# Dashboard_rev2.net
KiCad netlist of a schematic drawn in EAGLE
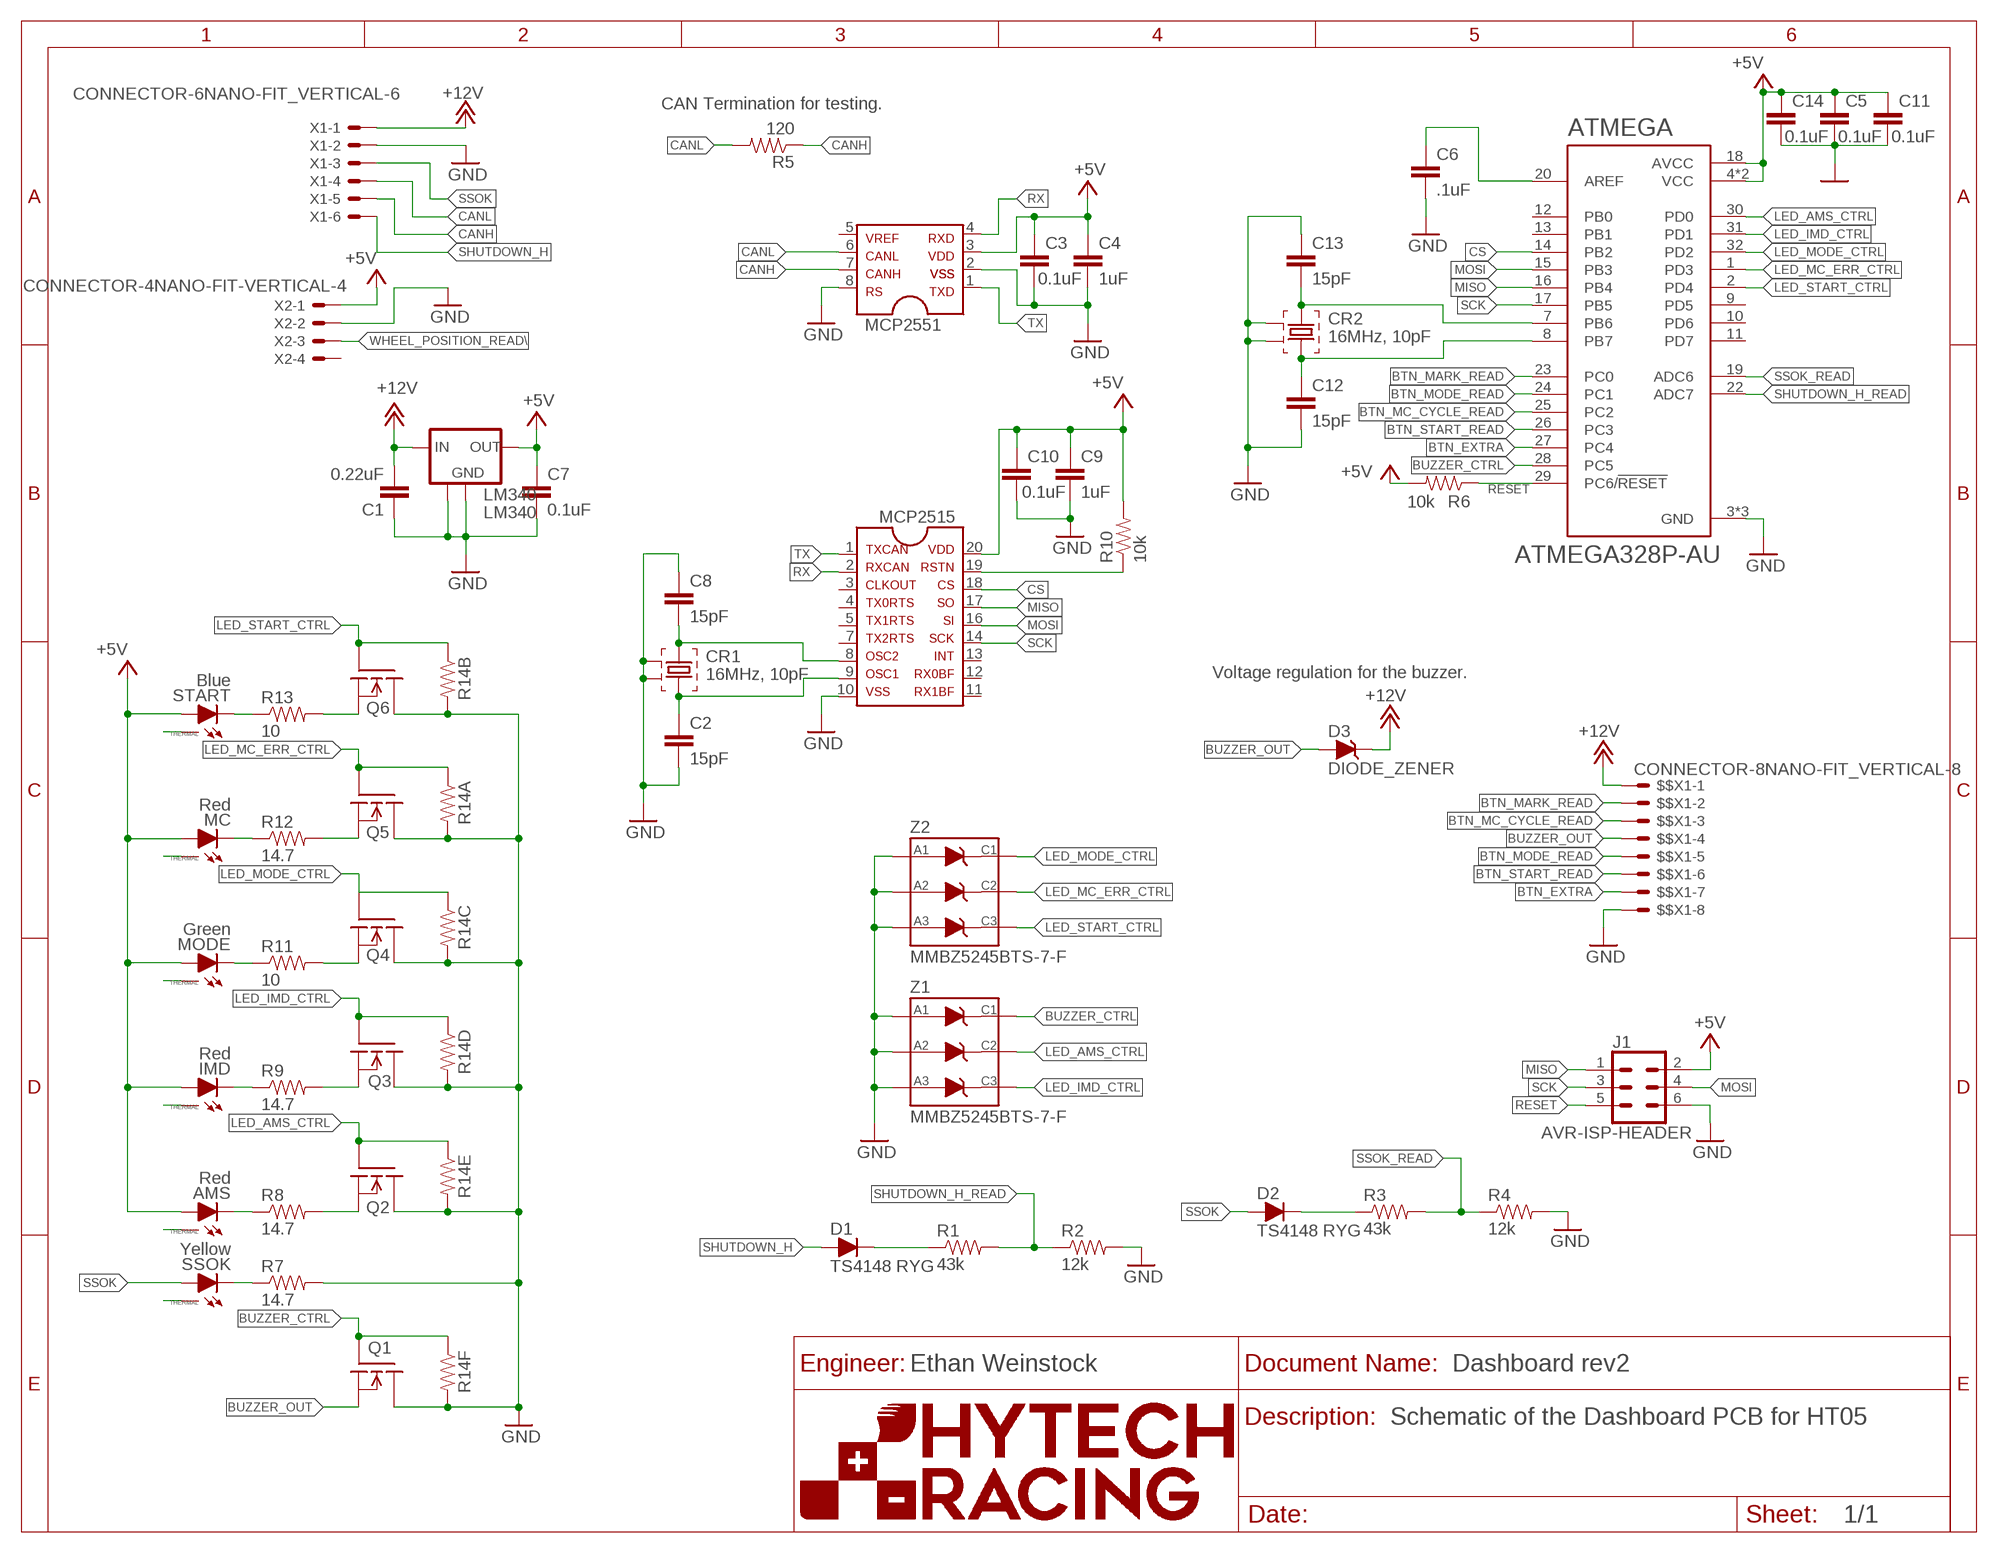
[diagram p0: schematic, sheet 1]

(export (version "E")
  (design (tool "Eeschema 10.0.6"))
  (components
    (comp (ref "$$X1")
      (value "CONNECTOR-8NANO-FIT_VERTICAL-8")
      (footprint "eagle-import:NANO-FIT_VERTICAL-8")
      (libsource (lib "eagle-import") (part "CONNECTOR-8NANO-FIT_VERTICAL-8"))
    )
    (comp (ref "AMS")
      (value "Red")
      (footprint "eagle-import:XP-E2")
      (libsource (lib "eagle-import") (part "XP-E2XP-E2"))
    )
    (comp (ref "ATMEGA")
      (value "ATMEGA328P-AU")
      (footprint "eagle-import:QFP80P900X900X120-32N")
      (fields (field (name "MF") "Microchip"))
      (libsource (lib "eagle-import") (part "ATMEGA328P-AU"))
    )
    (comp (ref "C1")
      (value "0.22uF")
      (footprint "eagle-import:0603-CAP")
      (libsource (lib "eagle-import") (part "CAP0603-CAP"))
    )
    (comp (ref "C2")
      (value "15pF")
      (footprint "eagle-import:0603-CAP")
      (libsource (lib "eagle-import") (part "CAP0603-CAP"))
    )
    (comp (ref "C3")
      (value "0.1uF")
      (footprint "eagle-import:0603-CAP")
      (libsource (lib "eagle-import") (part "CAP0603-CAP"))
    )
    (comp (ref "C4")
      (value "1uF")
      (footprint "eagle-import:0603-CAP")
      (libsource (lib "eagle-import") (part "CAP0603-CAP"))
    )
    (comp (ref "C5")
      (value "0.1uF")
      (footprint "eagle-import:0603-CAP")
      (libsource (lib "eagle-import") (part "CAP0603-CAP"))
    )
    (comp (ref "C6")
      (value ".1uF")
      (footprint "eagle-import:0603-CAP")
      (libsource (lib "eagle-import") (part "CAP0603-CAP"))
    )
    (comp (ref "C7")
      (value "0.1uF")
      (footprint "eagle-import:0603-CAP")
      (libsource (lib "eagle-import") (part "CAP0603-CAP"))
    )
    (comp (ref "C8")
      (value "15pF")
      (footprint "eagle-import:0603-CAP")
      (libsource (lib "eagle-import") (part "CAP0603-CAP"))
    )
    (comp (ref "C9")
      (value "1uF")
      (footprint "eagle-import:0603-CAP")
      (libsource (lib "eagle-import") (part "CAP0603-CAP"))
    )
    (comp (ref "C10")
      (value "0.1uF")
      (footprint "eagle-import:0603-CAP")
      (libsource (lib "eagle-import") (part "CAP0603-CAP"))
    )
    (comp (ref "C11")
      (value "0.1uF")
      (footprint "eagle-import:0603-CAP")
      (libsource (lib "eagle-import") (part "CAP0603-CAP"))
    )
    (comp (ref "C12")
      (value "15pF")
      (footprint "eagle-import:0603-CAP")
      (libsource (lib "eagle-import") (part "CAP0603-CAP"))
    )
    (comp (ref "C13")
      (value "15pF")
      (footprint "eagle-import:0603-CAP")
      (libsource (lib "eagle-import") (part "CAP0603-CAP"))
    )
    (comp (ref "C14")
      (value "0.1uF")
      (footprint "eagle-import:0603-CAP")
      (libsource (lib "eagle-import") (part "CAP0603-CAP"))
    )
    (comp (ref "CR1")
      (value "16MHz, 10pF")
      (footprint "eagle-import:ABM3B")
      (libsource (lib "eagle-import") (part "ABM3B"))
    )
    (comp (ref "CR2")
      (value "16MHz, 10pF")
      (footprint "eagle-import:ABM3B")
      (libsource (lib "eagle-import") (part "ABM3B"))
    )
    (comp (ref "D1")
      (value "TS4148 RYG")
      (footprint "eagle-import:0805_D")
      (libsource (lib "eagle-import") (part "DIODE0805"))
    )
    (comp (ref "D2")
      (value "TS4148 RYG")
      (footprint "eagle-import:0805_D")
      (libsource (lib "eagle-import") (part "DIODE0805"))
    )
    (comp (ref "D3")
      (value "DIODE_ZENER")
      (footprint "eagle-import:SOT23")
      (libsource (lib "eagle-import") (part "DIODE_ZENER"))
    )
    (comp (ref "IMD")
      (value "Red")
      (footprint "eagle-import:XP-E2")
      (libsource (lib "eagle-import") (part "XP-E2XP-E2"))
    )
    (comp (ref "J1")
      (value "AVR-ISP-HEADER")
      (footprint "eagle-import:2X03")
      (libsource (lib "eagle-import") (part "AVR-ISP-HEADER"))
    )
    (comp (ref "LM340")
      (value "LM340")
      (footprint "eagle-import:SOT223")
      (libsource (lib "eagle-import") (part "LM340"))
    )
    (comp (ref "MC")
      (value "Red")
      (footprint "eagle-import:XP-E2")
      (libsource (lib "eagle-import") (part "XP-E2XP-E2"))
    )
    (comp (ref "MCP2515")
      (value "MCP2515TSSOP")
      (footprint "eagle-import:TSSOP-20")
      (libsource (lib "eagle-import") (part "MCP2515TSSOP"))
    )
    (comp (ref "MCP2551")
      (value "MCP2551")
      (footprint "eagle-import:SOIC-08")
      (libsource (lib "eagle-import") (part "MCP2551"))
    )
    (comp (ref "MODE")
      (value "Green")
      (footprint "eagle-import:XP-E2")
      (libsource (lib "eagle-import") (part "XP-E2XP-E2"))
    )
    (comp (ref "Q1")
      (value "DMG3406LSOT")
      (footprint "eagle-import:SOT23")
      (libsource (lib "eagle-import") (part "DMG3406LSOT"))
    )
    (comp (ref "Q2")
      (value "DMG3406LSOT")
      (footprint "eagle-import:SOT23")
      (libsource (lib "eagle-import") (part "DMG3406LSOT"))
    )
    (comp (ref "Q3")
      (value "DMG3406LSOT")
      (footprint "eagle-import:SOT23")
      (libsource (lib "eagle-import") (part "DMG3406LSOT"))
    )
    (comp (ref "Q4")
      (value "DMG3406LSOT")
      (footprint "eagle-import:SOT23")
      (libsource (lib "eagle-import") (part "DMG3406LSOT"))
    )
    (comp (ref "Q5")
      (value "DMG3406LSOT")
      (footprint "eagle-import:SOT23")
      (libsource (lib "eagle-import") (part "DMG3406LSOT"))
    )
    (comp (ref "Q6")
      (value "DMG3406LSOT")
      (footprint "eagle-import:SOT23")
      (libsource (lib "eagle-import") (part "DMG3406LSOT"))
    )
    (comp (ref "R1")
      (value "43k")
      (footprint "eagle-import:0603-RES")
      (libsource (lib "eagle-import") (part "RESISTOR0603"))
    )
    (comp (ref "R2")
      (value "12k")
      (footprint "eagle-import:0603-RES")
      (libsource (lib "eagle-import") (part "RESISTOR0603"))
    )
    (comp (ref "R3")
      (value "43k")
      (footprint "eagle-import:0603-RES")
      (libsource (lib "eagle-import") (part "RESISTOR0603"))
    )
    (comp (ref "R4")
      (value "12k")
      (footprint "eagle-import:0603-RES")
      (libsource (lib "eagle-import") (part "RESISTOR0603"))
    )
    (comp (ref "R5")
      (value "120")
      (footprint "eagle-import:0603-RES")
      (libsource (lib "eagle-import") (part "RESISTOR0603-RES"))
    )
    (comp (ref "R6")
      (value "10k")
      (footprint "eagle-import:0603-RES")
      (libsource (lib "eagle-import") (part "RESISTOR0603"))
    )
    (comp (ref "R7")
      (value "14.7")
      (footprint "eagle-import:0603-RES")
      (libsource (lib "eagle-import") (part "RESISTOR0603"))
    )
    (comp (ref "R8")
      (value "14.7")
      (footprint "eagle-import:0603-RES")
      (libsource (lib "eagle-import") (part "RESISTOR0603"))
    )
    (comp (ref "R9")
      (value "14.7")
      (footprint "eagle-import:0603-RES")
      (libsource (lib "eagle-import") (part "RESISTOR0603"))
    )
    (comp (ref "R10")
      (value "10k")
      (footprint "eagle-import:0603-RES")
      (libsource (lib "eagle-import") (part "RESISTOR0603"))
    )
    (comp (ref "R11")
      (value "10")
      (footprint "eagle-import:0603-RES")
      (libsource (lib "eagle-import") (part "RESISTOR0603"))
    )
    (comp (ref "R12")
      (value "14.7")
      (footprint "eagle-import:0603-RES")
      (libsource (lib "eagle-import") (part "RESISTOR0603"))
    )
    (comp (ref "R13")
      (value "10")
      (footprint "eagle-import:0603-RES")
      (libsource (lib "eagle-import") (part "RESISTOR0603"))
    )
    (comp (ref "R14")
      (value "10k")
      (footprint "eagle-import:YAG_YC248-M")
      (fields (field (name "MANUFACTURER_PART_NUMBER") "YC248-JR-0710KL"))
      (libsource (lib "eagle-import") (part "YC248-JR-0710KL"))
    )
    (comp (ref "SSOK")
      (value "Yellow")
      (footprint "eagle-import:XP-E2")
      (libsource (lib "eagle-import") (part "XP-E2XP-E2"))
    )
    (comp (ref "START")
      (value "Blue")
      (footprint "eagle-import:XP-E2")
      (libsource (lib "eagle-import") (part "XP-E2XP-E2"))
    )
    (comp (ref "X1")
      (value "CONNECTOR-6NANO-FIT_VERTICAL-6")
      (footprint "eagle-import:NANO-FIT_VERTICAL-6")
      (libsource (lib "eagle-import") (part "CONNECTOR-6NANO-FIT_VERTICAL-6"))
    )
    (comp (ref "X2")
      (value "CONNECTOR-4NANO-FIT-VERTICAL-4")
      (footprint "eagle-import:NANO-FIT_VERTICAL-4")
      (libsource (lib "eagle-import") (part "CONNECTOR-4NANO-FIT-VERTICAL-4"))
    )
    (comp (ref "Z1")
      (value "MMBZ5245BTS-7-F")
      (footprint "eagle-import:SOT363")
      (fields (field (name "VOLTAGE") "15V"))
      (libsource (lib "eagle-import") (part "MMBZ5245BTS-7-F"))
    )
    (comp (ref "Z2")
      (value "MMBZ5245BTS-7-F")
      (footprint "eagle-import:SOT363")
      (fields (field (name "VOLTAGE") "15V"))
      (libsource (lib "eagle-import") (part "MMBZ5245BTS-7-F"))
    )
  )
  (nets
    (net (code "1") (name "+5V") (class "Default")
      (node (ref "AMS") (pin "A") (pinfunction "A_A") (pintype "passive"))
      (node (ref "ATMEGA") (pin "18") (pinfunction "AVCC_18") (pintype "power_in"))
      (node (ref "ATMEGA") (pin "4") (pinfunction "VCC_4") (pintype "power_in"))
      (node (ref "ATMEGA") (pin "6") (pinfunction "VCC_6") (pintype "power_in"))
      (node (ref "C10") (pin "1") (pinfunction "1_1") (pintype "passive"))
      (node (ref "C11") (pin "1") (pinfunction "1_1") (pintype "passive"))
      (node (ref "C14") (pin "1") (pinfunction "1_1") (pintype "passive"))
      (node (ref "C3") (pin "1") (pinfunction "1_1") (pintype "passive"))
      (node (ref "C4") (pin "1") (pinfunction "1_1") (pintype "passive"))
      (node (ref "C5") (pin "1") (pinfunction "1_1") (pintype "passive"))
      (node (ref "C7") (pin "1") (pinfunction "1_1") (pintype "passive"))
      (node (ref "C9") (pin "1") (pinfunction "1_1") (pintype "passive"))
      (node (ref "IMD") (pin "A") (pinfunction "A_A") (pintype "passive"))
      (node (ref "J1") (pin "2") (pinfunction "2_2") (pintype "passive"))
      (node (ref "LM340") (pin "3") (pinfunction "OUT_3") (pintype "output"))
      (node (ref "MC") (pin "A") (pinfunction "A_A") (pintype "passive"))
      (node (ref "MCP2515") (pin "20") (pinfunction "VDD_20") (pintype "passive"))
      (node (ref "MCP2551") (pin "3") (pinfunction "3_3") (pintype "passive"))
      (node (ref "MODE") (pin "A") (pinfunction "A_A") (pintype "passive"))
      (node (ref "R10") (pin "2") (pinfunction "2_2") (pintype "passive"))
      (node (ref "R6") (pin "2") (pinfunction "2_2") (pintype "passive"))
      (node (ref "START") (pin "A") (pinfunction "A_A") (pintype "passive"))
      (node (ref "X2") (pin "P$1") (pinfunction "S_P$1") (pintype "passive"))
    )
    (net (code "2") (name "+12V") (class "Default")
      (node (ref "$$X1") (pin "P$1") (pinfunction "S_P$1") (pintype "passive"))
      (node (ref "C1") (pin "2") (pinfunction "2_2") (pintype "passive"))
      (node (ref "D3") (pin "3") (pinfunction "C_3") (pintype "passive"))
      (node (ref "LM340") (pin "1") (pinfunction "IN_1") (pintype "input"))
      (node (ref "X1") (pin "P$1") (pinfunction "S_P$1") (pintype "passive"))
    )
    (net (code "3") (name "/THERMAL") (class "Default")
      (node (ref "AMS") (pin "X") (pinfunction "X_X") (pintype "passive"))
      (node (ref "IMD") (pin "X") (pinfunction "X_X") (pintype "passive"))
      (node (ref "MC") (pin "X") (pinfunction "X_X") (pintype "passive"))
      (node (ref "MODE") (pin "X") (pinfunction "X_X") (pintype "passive"))
      (node (ref "SSOK") (pin "X") (pinfunction "X_X") (pintype "passive"))
      (node (ref "START") (pin "X") (pinfunction "X_X") (pintype "passive"))
    )
    (net (code "4") (name "BTN_EXTRA") (class "Default")
      (node (ref "$$X1") (pin "P$7") (pinfunction "S_P$7") (pintype "passive"))
      (node (ref "ATMEGA") (pin "27") (pinfunction "PC4_27") (pintype "bidirectional"))
    )
    (net (code "5") (name "BTN_MARK_READ") (class "Default")
      (node (ref "$$X1") (pin "P$2") (pinfunction "S_P$2") (pintype "passive"))
      (node (ref "ATMEGA") (pin "23") (pinfunction "PC0_23") (pintype "bidirectional"))
    )
    (net (code "6") (name "BTN_MC_CYCLE_READ") (class "Default")
      (node (ref "$$X1") (pin "P$3") (pinfunction "S_P$3") (pintype "passive"))
      (node (ref "ATMEGA") (pin "25") (pinfunction "PC2_25") (pintype "bidirectional"))
    )
    (net (code "7") (name "BTN_MODE_READ") (class "Default")
      (node (ref "$$X1") (pin "P$5") (pinfunction "S_P$5") (pintype "passive"))
      (node (ref "ATMEGA") (pin "24") (pinfunction "PC1_24") (pintype "bidirectional"))
    )
    (net (code "8") (name "BTN_START_READ") (class "Default")
      (node (ref "$$X1") (pin "P$6") (pinfunction "S_P$6") (pintype "passive"))
      (node (ref "ATMEGA") (pin "26") (pinfunction "PC3_26") (pintype "bidirectional"))
    )
    (net (code "9") (name "BUZZER_CTRL") (class "Default")
      (node (ref "ATMEGA") (pin "28") (pinfunction "PC5_28") (pintype "bidirectional"))
      (node (ref "Q1") (pin "1") (pinfunction "G_1") (pintype "passive"))
      (node (ref "R14") (pin "6") (pinfunction "1_6") (pintype "passive"))
      (node (ref "Z1") (pin "P$4") (pinfunction "C1_P$4") (pintype "bidirectional"))
    )
    (net (code "10") (name "BUZZER_OUT") (class "Default")
      (node (ref "$$X1") (pin "P$4") (pinfunction "S_P$4") (pintype "passive"))
      (node (ref "D3") (pin "1") (pinfunction "A_1") (pintype "passive"))
      (node (ref "Q1") (pin "2") (pinfunction "S_2") (pintype "passive"))
    )
    (net (code "11") (name "CANH") (class "Default")
      (node (ref "MCP2551") (pin "7") (pinfunction "7_7") (pintype "passive"))
      (node (ref "R5") (pin "1") (pinfunction "1_1") (pintype "passive"))
      (node (ref "X1") (pin "P$5") (pinfunction "S_P$5") (pintype "passive"))
    )
    (net (code "12") (name "CANL") (class "Default")
      (node (ref "MCP2551") (pin "6") (pinfunction "6_6") (pintype "passive"))
      (node (ref "R5") (pin "2") (pinfunction "2_2") (pintype "passive"))
      (node (ref "X1") (pin "P$4") (pinfunction "S_P$4") (pintype "passive"))
    )
    (net (code "13") (name "CS") (class "Default")
      (node (ref "ATMEGA") (pin "14") (pinfunction "PB2_14") (pintype "bidirectional"))
      (node (ref "MCP2515") (pin "18") (pinfunction "CS_18") (pintype "passive"))
    )
    (net (code "14") (name "GND") (class "Default")
      (node (ref "$$X1") (pin "P$8") (pinfunction "S_P$8") (pintype "passive"))
      (node (ref "ATMEGA") (pin "21") (pinfunction "GND_21") (pintype "power_in"))
      (node (ref "ATMEGA") (pin "3") (pinfunction "GND_3") (pintype "power_in"))
      (node (ref "ATMEGA") (pin "5") (pinfunction "GND_5") (pintype "power_in"))
      (node (ref "C1") (pin "1") (pinfunction "1_1") (pintype "passive"))
      (node (ref "C10") (pin "2") (pinfunction "2_2") (pintype "passive"))
      (node (ref "C11") (pin "2") (pinfunction "2_2") (pintype "passive"))
      (node (ref "C12") (pin "2") (pinfunction "2_2") (pintype "passive"))
      (node (ref "C13") (pin "1") (pinfunction "1_1") (pintype "passive"))
      (node (ref "C14") (pin "2") (pinfunction "2_2") (pintype "passive"))
      (node (ref "C2") (pin "2") (pinfunction "2_2") (pintype "passive"))
      (node (ref "C3") (pin "2") (pinfunction "2_2") (pintype "passive"))
      (node (ref "C4") (pin "2") (pinfunction "2_2") (pintype "passive"))
      (node (ref "C5") (pin "2") (pinfunction "2_2") (pintype "passive"))
      (node (ref "C6") (pin "2") (pinfunction "2_2") (pintype "passive"))
      (node (ref "C7") (pin "2") (pinfunction "2_2") (pintype "passive"))
      (node (ref "C8") (pin "1") (pinfunction "1_1") (pintype "passive"))
      (node (ref "C9") (pin "2") (pinfunction "2_2") (pintype "passive"))
      (node (ref "CR1") (pin "P$2") (pinfunction "2_P$2") (pintype "passive"))
      (node (ref "CR1") (pin "P$4") (pinfunction "4_P$4") (pintype "passive"))
      (node (ref "CR2") (pin "P$2") (pinfunction "2_P$2") (pintype "passive"))
      (node (ref "CR2") (pin "P$4") (pinfunction "4_P$4") (pintype "passive"))
      (node (ref "J1") (pin "6") (pinfunction "6_6") (pintype "passive"))
      (node (ref "LM340") (pin "2") (pinfunction "GND_2") (pintype "input"))
      (node (ref "LM340") (pin "4") (pinfunction "GND1_4") (pintype "input"))
      (node (ref "MCP2515") (pin "10") (pinfunction "VSS_10") (pintype "passive"))
      (node (ref "MCP2551") (pin "2") (pinfunction "2_2") (pintype "passive"))
      (node (ref "MCP2551") (pin "8") (pinfunction "8_8") (pintype "passive"))
      (node (ref "Q1") (pin "3") (pinfunction "D_3") (pintype "passive"))
      (node (ref "Q2") (pin "3") (pinfunction "D_3") (pintype "passive"))
      (node (ref "Q3") (pin "3") (pinfunction "D_3") (pintype "passive"))
      (node (ref "Q4") (pin "3") (pinfunction "D_3") (pintype "passive"))
      (node (ref "Q5") (pin "3") (pinfunction "D_3") (pintype "passive"))
      (node (ref "Q6") (pin "3") (pinfunction "D_3") (pintype "passive"))
      (node (ref "R14") (pin "11") (pinfunction "2_11") (pintype "passive"))
      (node (ref "R14") (pin "12") (pinfunction "2_12") (pintype "passive"))
      (node (ref "R14") (pin "13") (pinfunction "2_13") (pintype "passive"))
      (node (ref "R14") (pin "14") (pinfunction "2_14") (pintype "passive"))
      (node (ref "R14") (pin "15") (pinfunction "2_15") (pintype "passive"))
      (node (ref "R14") (pin "16") (pinfunction "2_16") (pintype "passive"))
      (node (ref "R2") (pin "2") (pinfunction "2_2") (pintype "passive"))
      (node (ref "R4") (pin "2") (pinfunction "2_2") (pintype "passive"))
      (node (ref "R7") (pin "2") (pinfunction "2_2") (pintype "passive"))
      (node (ref "X1") (pin "P$2") (pinfunction "S_P$2") (pintype "passive"))
      (node (ref "X2") (pin "P$2") (pinfunction "S_P$2") (pintype "passive"))
      (node (ref "Z1") (pin "P$1") (pinfunction "A1_P$1") (pintype "bidirectional"))
      (node (ref "Z1") (pin "P$2") (pinfunction "A2_P$2") (pintype "bidirectional"))
      (node (ref "Z1") (pin "P$3") (pinfunction "A3_P$3") (pintype "bidirectional"))
      (node (ref "Z2") (pin "P$1") (pinfunction "A1_P$1") (pintype "bidirectional"))
      (node (ref "Z2") (pin "P$2") (pinfunction "A2_P$2") (pintype "bidirectional"))
      (node (ref "Z2") (pin "P$3") (pinfunction "A3_P$3") (pintype "bidirectional"))
    )
    (net (code "15") (name "LED_AMS_CTRL") (class "Default")
      (node (ref "ATMEGA") (pin "30") (pinfunction "PD0_30") (pintype "bidirectional"))
      (node (ref "Q2") (pin "1") (pinfunction "G_1") (pintype "passive"))
      (node (ref "R14") (pin "5") (pinfunction "1_5") (pintype "passive"))
      (node (ref "Z1") (pin "P$5") (pinfunction "C2_P$5") (pintype "bidirectional"))
    )
    (net (code "16") (name "LED_IMD_CTRL") (class "Default")
      (node (ref "ATMEGA") (pin "31") (pinfunction "PD1_31") (pintype "bidirectional"))
      (node (ref "Q3") (pin "1") (pinfunction "G_1") (pintype "passive"))
      (node (ref "R14") (pin "4") (pinfunction "1_4") (pintype "passive"))
      (node (ref "Z1") (pin "P$6") (pinfunction "C3_P$6") (pintype "bidirectional"))
    )
    (net (code "17") (name "LED_MC_ERR_CTRL") (class "Default")
      (node (ref "ATMEGA") (pin "1") (pinfunction "PD3_1") (pintype "bidirectional"))
      (node (ref "Q5") (pin "1") (pinfunction "G_1") (pintype "passive"))
      (node (ref "R14") (pin "1") (pinfunction "1_1") (pintype "passive"))
      (node (ref "Z2") (pin "P$5") (pinfunction "C2_P$5") (pintype "bidirectional"))
    )
    (net (code "18") (name "LED_MODE_CTRL") (class "Default")
      (node (ref "ATMEGA") (pin "32") (pinfunction "PD2_32") (pintype "bidirectional"))
      (node (ref "Q4") (pin "1") (pinfunction "G_1") (pintype "passive"))
      (node (ref "R14") (pin "3") (pinfunction "1_3") (pintype "passive"))
      (node (ref "Z2") (pin "P$4") (pinfunction "C1_P$4") (pintype "bidirectional"))
    )
    (net (code "19") (name "LED_START_CTRL") (class "Default")
      (node (ref "ATMEGA") (pin "2") (pinfunction "PD4_2") (pintype "bidirectional"))
      (node (ref "Q6") (pin "1") (pinfunction "G_1") (pintype "passive"))
      (node (ref "R14") (pin "2") (pinfunction "1_2") (pintype "passive"))
      (node (ref "Z2") (pin "P$6") (pinfunction "C3_P$6") (pintype "bidirectional"))
    )
    (net (code "20") (name "MISO") (class "Default")
      (node (ref "ATMEGA") (pin "16") (pinfunction "PB4_16") (pintype "bidirectional"))
      (node (ref "J1") (pin "1") (pinfunction "1_1") (pintype "passive"))
      (node (ref "MCP2515") (pin "17") (pinfunction "SO_17") (pintype "passive"))
    )
    (net (code "21") (name "MOSI") (class "Default")
      (node (ref "ATMEGA") (pin "15") (pinfunction "PB3_15") (pintype "bidirectional"))
      (node (ref "J1") (pin "4") (pinfunction "4_4") (pintype "passive"))
      (node (ref "MCP2515") (pin "16") (pinfunction "SI_16") (pintype "passive"))
    )
    (net (code "22") (name "Net-(AMS-PadC)") (class "Default")
      (node (ref "AMS") (pin "C") (pinfunction "C_C") (pintype "passive"))
      (node (ref "R8") (pin "1") (pinfunction "1_1") (pintype "passive"))
    )
    (net (code "23") (name "Net-(ATMEGA-AREF)") (class "Default")
      (node (ref "ATMEGA") (pin "20") (pinfunction "AREF_20") (pintype "input"))
      (node (ref "C6") (pin "1") (pinfunction "1_1") (pintype "passive"))
    )
    (net (code "24") (name "Net-(ATMEGA-PB6)") (class "Default")
      (node (ref "ATMEGA") (pin "7") (pinfunction "PB6_7") (pintype "bidirectional"))
      (node (ref "C13") (pin "2") (pinfunction "2_2") (pintype "passive"))
      (node (ref "CR2") (pin "P$1") (pinfunction "1_P$1") (pintype "passive"))
    )
    (net (code "25") (name "Net-(ATMEGA-PB7)") (class "Default")
      (node (ref "ATMEGA") (pin "8") (pinfunction "PB7_8") (pintype "bidirectional"))
      (node (ref "C12") (pin "1") (pinfunction "1_1") (pintype "passive"))
      (node (ref "CR2") (pin "P$3") (pinfunction "3_P$3") (pintype "passive"))
    )
    (net (code "26") (name "Net-(CR1-1)") (class "Default")
      (node (ref "C8") (pin "2") (pinfunction "2_2") (pintype "passive"))
      (node (ref "CR1") (pin "P$1") (pinfunction "1_P$1") (pintype "passive"))
      (node (ref "MCP2515") (pin "8") (pinfunction "OSC2_8") (pintype "passive"))
    )
    (net (code "27") (name "Net-(CR1-3)") (class "Default")
      (node (ref "C2") (pin "1") (pinfunction "1_1") (pintype "passive"))
      (node (ref "CR1") (pin "P$3") (pinfunction "3_P$3") (pintype "passive"))
      (node (ref "MCP2515") (pin "9") (pinfunction "OSC1_9") (pintype "passive"))
    )
    (net (code "28") (name "Net-(D1-PadC)") (class "Default")
      (node (ref "D1") (pin "C") (pinfunction "C_C") (pintype "passive"))
      (node (ref "R1") (pin "1") (pinfunction "1_1") (pintype "passive"))
    )
    (net (code "29") (name "Net-(D2-PadC)") (class "Default")
      (node (ref "D2") (pin "C") (pinfunction "C_C") (pintype "passive"))
      (node (ref "R3") (pin "1") (pinfunction "1_1") (pintype "passive"))
    )
    (net (code "30") (name "Net-(IMD-PadC)") (class "Default")
      (node (ref "IMD") (pin "C") (pinfunction "C_C") (pintype "passive"))
      (node (ref "R9") (pin "1") (pinfunction "1_1") (pintype "passive"))
    )
    (net (code "31") (name "Net-(MC-PadC)") (class "Default")
      (node (ref "MC") (pin "C") (pinfunction "C_C") (pintype "passive"))
      (node (ref "R12") (pin "1") (pinfunction "1_1") (pintype "passive"))
    )
    (net (code "32") (name "Net-(MCP2515-RSTN)") (class "Default")
      (node (ref "MCP2515") (pin "19") (pinfunction "RSTN_19") (pintype "passive"))
      (node (ref "R10") (pin "1") (pinfunction "1_1") (pintype "passive"))
    )
    (net (code "33") (name "Net-(MODE-PadC)") (class "Default")
      (node (ref "MODE") (pin "C") (pinfunction "C_C") (pintype "passive"))
      (node (ref "R11") (pin "1") (pinfunction "1_1") (pintype "passive"))
    )
    (net (code "34") (name "Net-(Q2-S)") (class "Default")
      (node (ref "Q2") (pin "2") (pinfunction "S_2") (pintype "passive"))
      (node (ref "R8") (pin "2") (pinfunction "2_2") (pintype "passive"))
    )
    (net (code "35") (name "Net-(Q3-S)") (class "Default")
      (node (ref "Q3") (pin "2") (pinfunction "S_2") (pintype "passive"))
      (node (ref "R9") (pin "2") (pinfunction "2_2") (pintype "passive"))
    )
    (net (code "36") (name "Net-(Q4-S)") (class "Default")
      (node (ref "Q4") (pin "2") (pinfunction "S_2") (pintype "passive"))
      (node (ref "R11") (pin "2") (pinfunction "2_2") (pintype "passive"))
    )
    (net (code "37") (name "Net-(Q5-S)") (class "Default")
      (node (ref "Q5") (pin "2") (pinfunction "S_2") (pintype "passive"))
      (node (ref "R12") (pin "2") (pinfunction "2_2") (pintype "passive"))
    )
    (net (code "38") (name "Net-(Q6-S)") (class "Default")
      (node (ref "Q6") (pin "2") (pinfunction "S_2") (pintype "passive"))
      (node (ref "R13") (pin "2") (pinfunction "2_2") (pintype "passive"))
    )
    (net (code "39") (name "Net-(R7-Pad1)") (class "Default")
      (node (ref "R7") (pin "1") (pinfunction "1_1") (pintype "passive"))
      (node (ref "SSOK") (pin "C") (pinfunction "C_C") (pintype "passive"))
    )
    (net (code "40") (name "Net-(R13-Pad1)") (class "Default")
      (node (ref "R13") (pin "1") (pinfunction "1_1") (pintype "passive"))
      (node (ref "START") (pin "C") (pinfunction "C_C") (pintype "passive"))
    )
    (net (code "41") (name "RESET") (class "Default")
      (node (ref "ATMEGA") (pin "29") (pinfunction "PC6/~{RESET}_29") (pintype "bidirectional"))
      (node (ref "J1") (pin "5") (pinfunction "5_5") (pintype "passive"))
      (node (ref "R6") (pin "1") (pinfunction "1_1") (pintype "passive"))
    )
    (net (code "42") (name "RX") (class "Default")
      (node (ref "MCP2515") (pin "2") (pinfunction "RXCAN_2") (pintype "passive"))
      (node (ref "MCP2551") (pin "4") (pinfunction "4_4") (pintype "passive"))
    )
    (net (code "43") (name "SCK") (class "Default")
      (node (ref "ATMEGA") (pin "17") (pinfunction "PB5_17") (pintype "bidirectional"))
      (node (ref "J1") (pin "3") (pinfunction "3_3") (pintype "passive"))
      (node (ref "MCP2515") (pin "14") (pinfunction "SCK_14") (pintype "passive"))
    )
    (net (code "44") (name "SHUTDOWN_H") (class "Default")
      (node (ref "D1") (pin "A") (pinfunction "A_A") (pintype "passive"))
      (node (ref "X1") (pin "P$6") (pinfunction "S_P$6") (pintype "passive"))
    )
    (net (code "45") (name "SHUTDOWN_H_READ") (class "Default")
      (node (ref "ATMEGA") (pin "22") (pinfunction "ADC7_22") (pintype "bidirectional"))
      (node (ref "R1") (pin "2") (pinfunction "2_2") (pintype "passive"))
      (node (ref "R2") (pin "1") (pinfunction "1_1") (pintype "passive"))
    )
    (net (code "46") (name "SSOK") (class "Default")
      (node (ref "D2") (pin "A") (pinfunction "A_A") (pintype "passive"))
      (node (ref "SSOK") (pin "A") (pinfunction "A_A") (pintype "passive"))
      (node (ref "X1") (pin "P$3") (pinfunction "S_P$3") (pintype "passive"))
    )
    (net (code "47") (name "SSOK_READ") (class "Default")
      (node (ref "ATMEGA") (pin "19") (pinfunction "ADC6_19") (pintype "bidirectional"))
      (node (ref "R3") (pin "2") (pinfunction "2_2") (pintype "passive"))
      (node (ref "R4") (pin "1") (pinfunction "1_1") (pintype "passive"))
    )
    (net (code "48") (name "TX") (class "Default")
      (node (ref "MCP2515") (pin "1") (pinfunction "TXCAN_1") (pintype "passive"))
      (node (ref "MCP2551") (pin "1") (pinfunction "1_1") (pintype "passive"))
    )
    (net (code "49") (name "WHEEL_POSITION_READ\\") (class "Default")
      (node (ref "X2") (pin "P$3") (pinfunction "S_P$3") (pintype "passive"))
    )
    (net (code "50") (name "unconnected-(ATMEGA-PB0-Pad12)") (class "Default")
      (node (ref "ATMEGA") (pin "12") (pinfunction "PB0_12") (pintype "bidirectional"))
    )
    (net (code "51") (name "unconnected-(ATMEGA-PB1-Pad13)") (class "Default")
      (node (ref "ATMEGA") (pin "13") (pinfunction "PB1_13") (pintype "bidirectional"))
    )
    (net (code "52") (name "unconnected-(ATMEGA-PD5-Pad9)") (class "Default")
      (node (ref "ATMEGA") (pin "9") (pinfunction "PD5_9") (pintype "bidirectional"))
    )
    (net (code "53") (name "unconnected-(ATMEGA-PD6-Pad10)") (class "Default")
      (node (ref "ATMEGA") (pin "10") (pinfunction "PD6_10") (pintype "bidirectional"))
    )
    (net (code "54") (name "unconnected-(ATMEGA-PD7-Pad11)") (class "Default")
      (node (ref "ATMEGA") (pin "11") (pinfunction "PD7_11") (pintype "bidirectional"))
    )
    (net (code "55") (name "unconnected-(MCP2515-CLKOUT-Pad3)") (class "Default")
      (node (ref "MCP2515") (pin "3") (pinfunction "CLKOUT_3") (pintype "passive"))
    )
    (net (code "56") (name "unconnected-(MCP2515-INT-Pad13)") (class "Default")
      (node (ref "MCP2515") (pin "13") (pinfunction "INT_13") (pintype "passive"))
    )
    (net (code "57") (name "unconnected-(MCP2515-RX0BF-Pad12)") (class "Default")
      (node (ref "MCP2515") (pin "12") (pinfunction "RX0BF_12") (pintype "passive"))
    )
    (net (code "58") (name "unconnected-(MCP2515-RX1BF-Pad11)") (class "Default")
      (node (ref "MCP2515") (pin "11") (pinfunction "RX1BF_11") (pintype "passive"))
    )
    (net (code "59") (name "unconnected-(MCP2515-TX0RTS-Pad4)") (class "Default")
      (node (ref "MCP2515") (pin "4") (pinfunction "TX0RTS_4") (pintype "passive"))
    )
    (net (code "60") (name "unconnected-(MCP2515-TX1RTS-Pad5)") (class "Default")
      (node (ref "MCP2515") (pin "5") (pinfunction "TX1RTS_5") (pintype "passive"))
    )
    (net (code "61") (name "unconnected-(MCP2515-TX2RTS-Pad7)") (class "Default")
      (node (ref "MCP2515") (pin "7") (pinfunction "TX2RTS_7") (pintype "passive"))
    )
    (net (code "62") (name "unconnected-(MCP2551-Pad5)") (class "Default")
      (node (ref "MCP2551") (pin "5") (pinfunction "5_5") (pintype "passive"))
    )
    (net (code "63") (name "unconnected-(X2D-S-PadP$4)") (class "Default")
      (node (ref "X2") (pin "P$4") (pinfunction "S_P$4") (pintype "passive"))
    )
  )
)
